# 2126_A_MatrixBoard_AffichageMatricielNom.net
KiCad netlist of a schematic drawn in Altium Designer
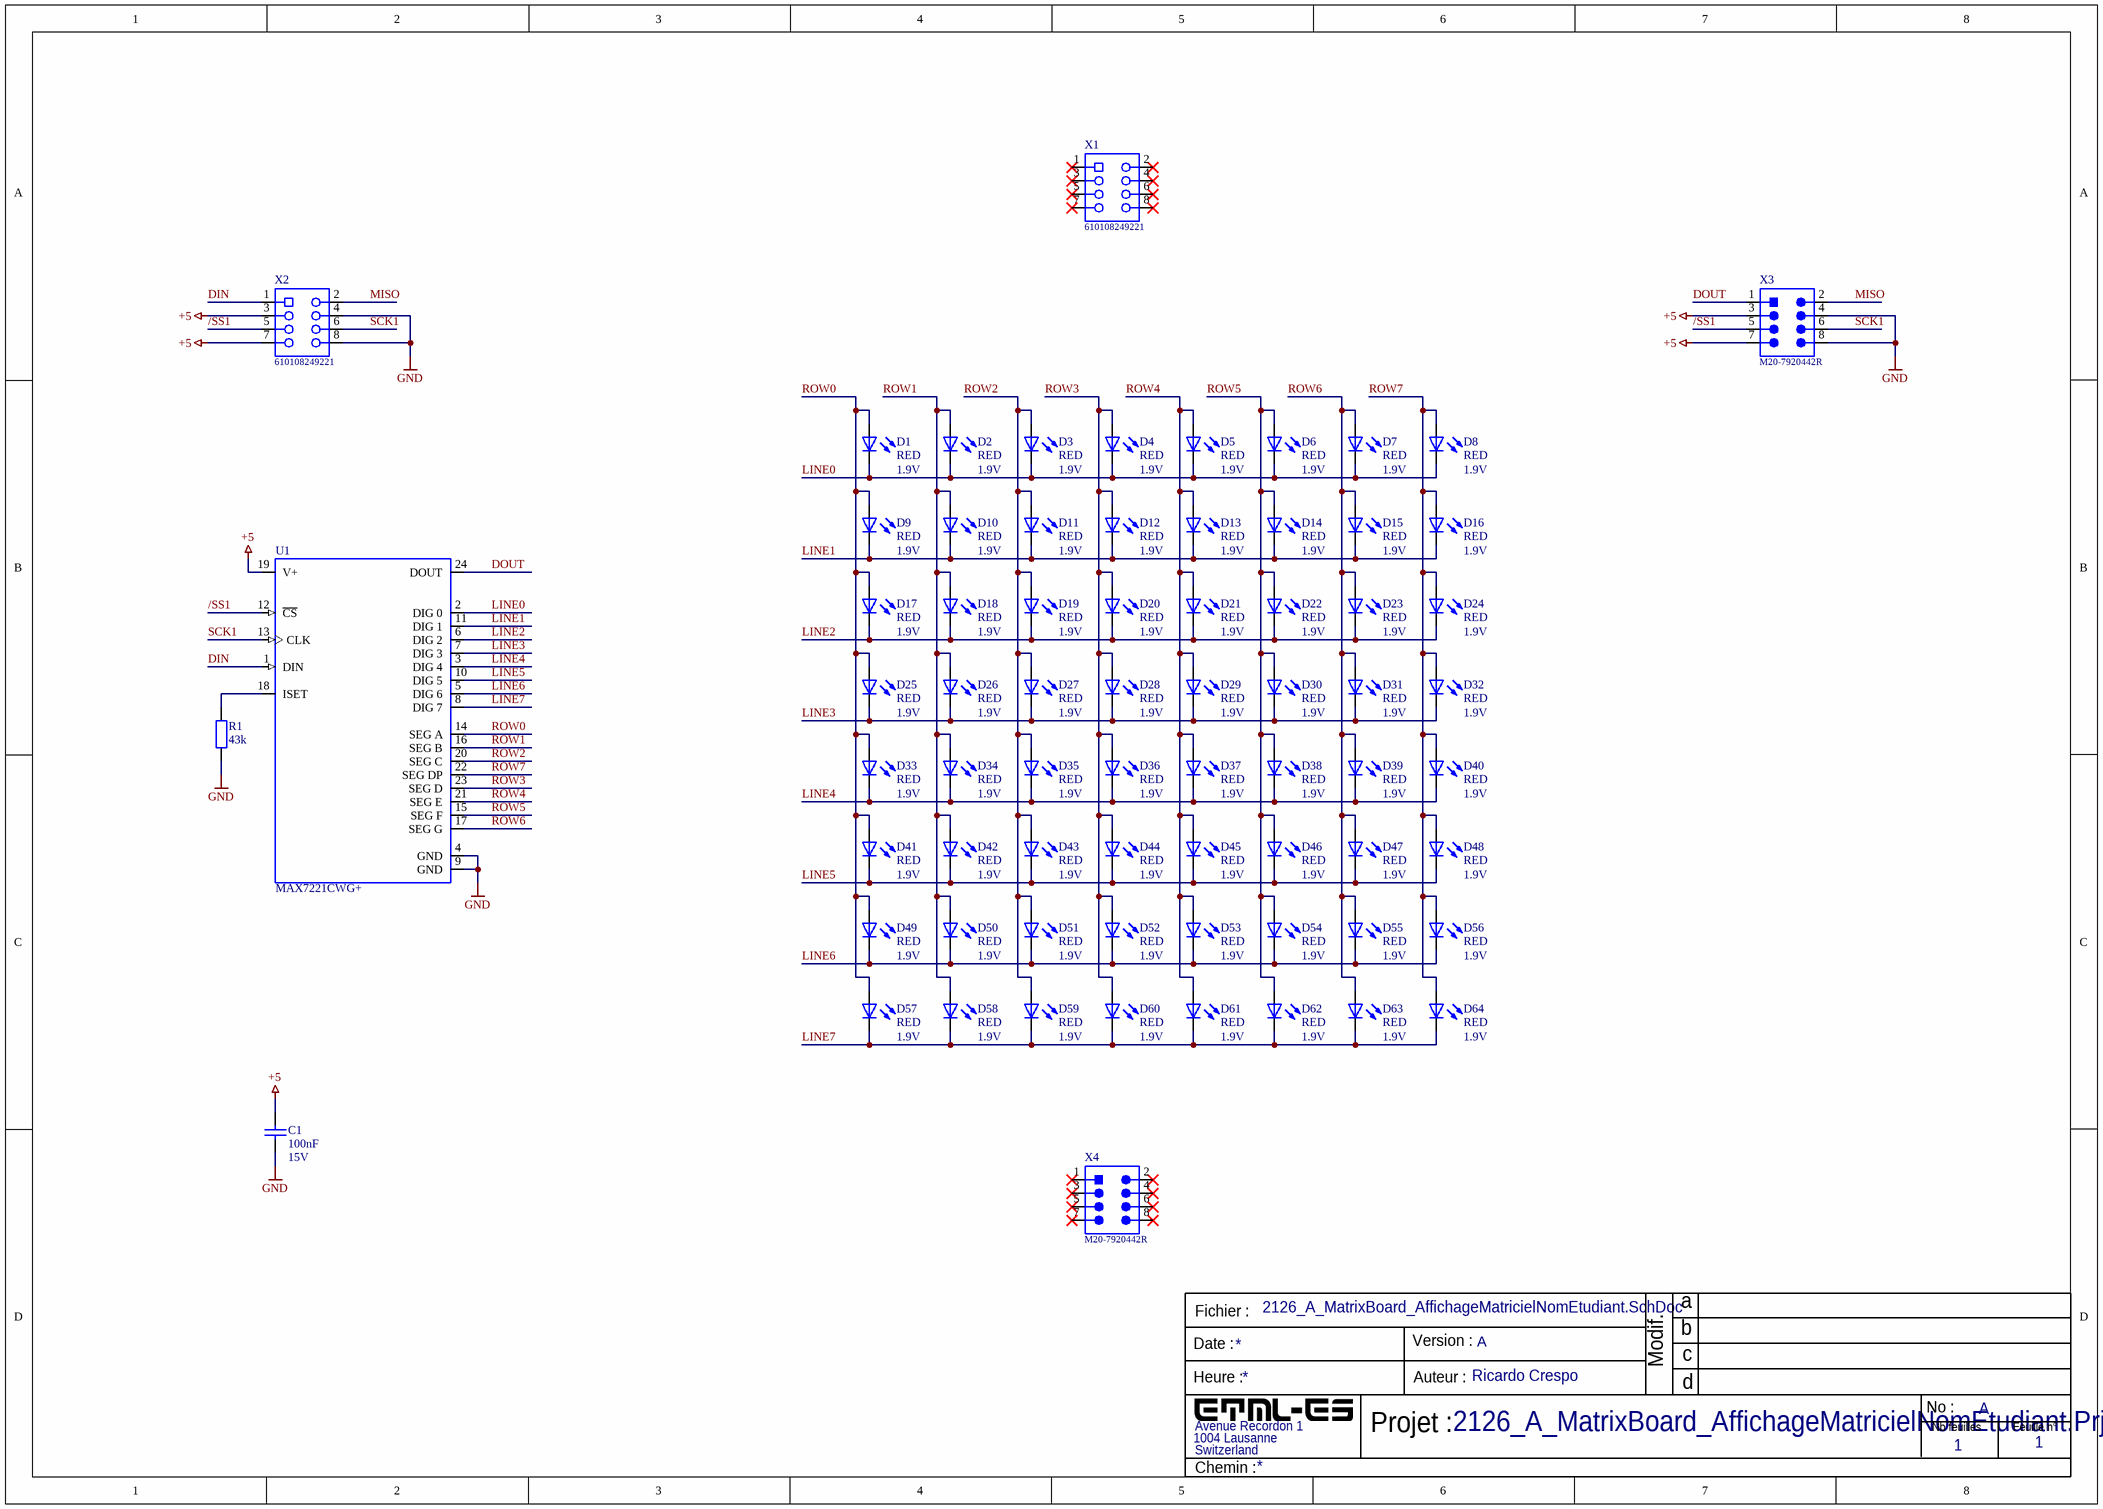
[diagram p0: 2126_A_MatrixBoard_AffichageMatricielNomEtudiant.SchDoc]

(export (version "E")
  (design (tool "Eeschema 10.0.6"))
  (components
    (comp (ref "C1")
      (value "100nF")
      (footprint "CAPC2013X145X48NL20T23")
      (description "VJ0805Y104KNAAT")
      (fields (field (name "MANUFACTURER") "Vitramon"))
      (libsource (lib "2126_AffichageMatriciel") (part "CMP-2007-03167-1"))
    )
    (comp (ref "D1")
      (value "RED")
      (footprint "SODFL350X210-2N")
      (description "WL-TMRC THT Mono-color Round Color, size 3mm, Bright Green, 2.1V, 40deg")
      (fields (field (name "PART NUMBER") "151031VS04000") (field (name "PUBLISHER") "Wurth Elektronik"))
      (libsource (lib "2126_AffichageMatriciel") (part "151031VS04000"))
    )
    (comp (ref "D2")
      (value "RED")
      (footprint "SODFL350X210-2N")
      (description "WL-TMRC THT Mono-color Round Color, size 3mm, Bright Green, 2.1V, 40deg")
      (fields (field (name "PART NUMBER") "151031VS04000") (field (name "PUBLISHER") "Wurth Elektronik"))
      (libsource (lib "2126_AffichageMatriciel") (part "151031VS04000"))
    )
    (comp (ref "D3")
      (value "RED")
      (footprint "SODFL350X210-2N")
      (description "WL-TMRC THT Mono-color Round Color, size 3mm, Bright Green, 2.1V, 40deg")
      (fields (field (name "PART NUMBER") "151031VS04000") (field (name "PUBLISHER") "Wurth Elektronik"))
      (libsource (lib "2126_AffichageMatriciel") (part "151031VS04000"))
    )
    (comp (ref "D4")
      (value "RED")
      (footprint "SODFL350X210-2N")
      (description "WL-TMRC THT Mono-color Round Color, size 3mm, Bright Green, 2.1V, 40deg")
      (fields (field (name "PART NUMBER") "151031VS04000") (field (name "PUBLISHER") "Wurth Elektronik"))
      (libsource (lib "2126_AffichageMatriciel") (part "151031VS04000"))
    )
    (comp (ref "D5")
      (value "RED")
      (footprint "SODFL350X210-2N")
      (description "WL-TMRC THT Mono-color Round Color, size 3mm, Bright Green, 2.1V, 40deg")
      (fields (field (name "PART NUMBER") "151031VS04000") (field (name "PUBLISHER") "Wurth Elektronik"))
      (libsource (lib "2126_AffichageMatriciel") (part "151031VS04000"))
    )
    (comp (ref "D6")
      (value "RED")
      (footprint "SODFL350X210-2N")
      (description "WL-TMRC THT Mono-color Round Color, size 3mm, Bright Green, 2.1V, 40deg")
      (fields (field (name "PART NUMBER") "151031VS04000") (field (name "PUBLISHER") "Wurth Elektronik"))
      (libsource (lib "2126_AffichageMatriciel") (part "151031VS04000"))
    )
    (comp (ref "D7")
      (value "RED")
      (footprint "SODFL350X210-2N")
      (description "WL-TMRC THT Mono-color Round Color, size 3mm, Bright Green, 2.1V, 40deg")
      (fields (field (name "PART NUMBER") "151031VS04000") (field (name "PUBLISHER") "Wurth Elektronik"))
      (libsource (lib "2126_AffichageMatriciel") (part "151031VS04000"))
    )
    (comp (ref "D8")
      (value "RED")
      (footprint "SODFL350X210-2N")
      (description "WL-TMRC THT Mono-color Round Color, size 3mm, Bright Green, 2.1V, 40deg")
      (fields (field (name "PART NUMBER") "151031VS04000") (field (name "PUBLISHER") "Wurth Elektronik"))
      (libsource (lib "2126_AffichageMatriciel") (part "151031VS04000"))
    )
    (comp (ref "D9")
      (value "RED")
      (footprint "SODFL350X210-2N")
      (description "WL-TMRC THT Mono-color Round Color, size 3mm, Bright Green, 2.1V, 40deg")
      (fields (field (name "PART NUMBER") "151031VS04000") (field (name "PUBLISHER") "Wurth Elektronik"))
      (libsource (lib "2126_AffichageMatriciel") (part "151031VS04000"))
    )
    (comp (ref "D10")
      (value "RED")
      (footprint "SODFL350X210-2N")
      (description "WL-TMRC THT Mono-color Round Color, size 3mm, Bright Green, 2.1V, 40deg")
      (fields (field (name "PART NUMBER") "151031VS04000") (field (name "PUBLISHER") "Wurth Elektronik"))
      (libsource (lib "2126_AffichageMatriciel") (part "151031VS04000"))
    )
    (comp (ref "D11")
      (value "RED")
      (footprint "SODFL350X210-2N")
      (description "WL-TMRC THT Mono-color Round Color, size 3mm, Bright Green, 2.1V, 40deg")
      (fields (field (name "PART NUMBER") "151031VS04000") (field (name "PUBLISHER") "Wurth Elektronik"))
      (libsource (lib "2126_AffichageMatriciel") (part "151031VS04000"))
    )
    (comp (ref "D12")
      (value "RED")
      (footprint "SODFL350X210-2N")
      (description "WL-TMRC THT Mono-color Round Color, size 3mm, Bright Green, 2.1V, 40deg")
      (fields (field (name "PART NUMBER") "151031VS04000") (field (name "PUBLISHER") "Wurth Elektronik"))
      (libsource (lib "2126_AffichageMatriciel") (part "151031VS04000"))
    )
    (comp (ref "D13")
      (value "RED")
      (footprint "SODFL350X210-2N")
      (description "WL-TMRC THT Mono-color Round Color, size 3mm, Bright Green, 2.1V, 40deg")
      (fields (field (name "PART NUMBER") "151031VS04000") (field (name "PUBLISHER") "Wurth Elektronik"))
      (libsource (lib "2126_AffichageMatriciel") (part "151031VS04000"))
    )
    (comp (ref "D14")
      (value "RED")
      (footprint "SODFL350X210-2N")
      (description "WL-TMRC THT Mono-color Round Color, size 3mm, Bright Green, 2.1V, 40deg")
      (fields (field (name "PART NUMBER") "151031VS04000") (field (name "PUBLISHER") "Wurth Elektronik"))
      (libsource (lib "2126_AffichageMatriciel") (part "151031VS04000"))
    )
    (comp (ref "D15")
      (value "RED")
      (footprint "SODFL350X210-2N")
      (description "WL-TMRC THT Mono-color Round Color, size 3mm, Bright Green, 2.1V, 40deg")
      (fields (field (name "PART NUMBER") "151031VS04000") (field (name "PUBLISHER") "Wurth Elektronik"))
      (libsource (lib "2126_AffichageMatriciel") (part "151031VS04000"))
    )
    (comp (ref "D16")
      (value "RED")
      (footprint "SODFL350X210-2N")
      (description "WL-TMRC THT Mono-color Round Color, size 3mm, Bright Green, 2.1V, 40deg")
      (fields (field (name "PART NUMBER") "151031VS04000") (field (name "PUBLISHER") "Wurth Elektronik"))
      (libsource (lib "2126_AffichageMatriciel") (part "151031VS04000"))
    )
    (comp (ref "D17")
      (value "RED")
      (footprint "SODFL350X210-2N")
      (description "WL-TMRC THT Mono-color Round Color, size 3mm, Bright Green, 2.1V, 40deg")
      (fields (field (name "PART NUMBER") "151031VS04000") (field (name "PUBLISHER") "Wurth Elektronik"))
      (libsource (lib "2126_AffichageMatriciel") (part "151031VS04000"))
    )
    (comp (ref "D18")
      (value "RED")
      (footprint "SODFL350X210-2N")
      (description "WL-TMRC THT Mono-color Round Color, size 3mm, Bright Green, 2.1V, 40deg")
      (fields (field (name "PART NUMBER") "151031VS04000") (field (name "PUBLISHER") "Wurth Elektronik"))
      (libsource (lib "2126_AffichageMatriciel") (part "151031VS04000"))
    )
    (comp (ref "D19")
      (value "RED")
      (footprint "SODFL350X210-2N")
      (description "WL-TMRC THT Mono-color Round Color, size 3mm, Bright Green, 2.1V, 40deg")
      (fields (field (name "PART NUMBER") "151031VS04000") (field (name "PUBLISHER") "Wurth Elektronik"))
      (libsource (lib "2126_AffichageMatriciel") (part "151031VS04000"))
    )
    (comp (ref "D20")
      (value "RED")
      (footprint "SODFL350X210-2N")
      (description "WL-TMRC THT Mono-color Round Color, size 3mm, Bright Green, 2.1V, 40deg")
      (fields (field (name "PART NUMBER") "151031VS04000") (field (name "PUBLISHER") "Wurth Elektronik"))
      (libsource (lib "2126_AffichageMatriciel") (part "151031VS04000"))
    )
    (comp (ref "D21")
      (value "RED")
      (footprint "SODFL350X210-2N")
      (description "WL-TMRC THT Mono-color Round Color, size 3mm, Bright Green, 2.1V, 40deg")
      (fields (field (name "PART NUMBER") "151031VS04000") (field (name "PUBLISHER") "Wurth Elektronik"))
      (libsource (lib "2126_AffichageMatriciel") (part "151031VS04000"))
    )
    (comp (ref "D22")
      (value "RED")
      (footprint "SODFL350X210-2N")
      (description "WL-TMRC THT Mono-color Round Color, size 3mm, Bright Green, 2.1V, 40deg")
      (fields (field (name "PART NUMBER") "151031VS04000") (field (name "PUBLISHER") "Wurth Elektronik"))
      (libsource (lib "2126_AffichageMatriciel") (part "151031VS04000"))
    )
    (comp (ref "D23")
      (value "RED")
      (footprint "SODFL350X210-2N")
      (description "WL-TMRC THT Mono-color Round Color, size 3mm, Bright Green, 2.1V, 40deg")
      (fields (field (name "PART NUMBER") "151031VS04000") (field (name "PUBLISHER") "Wurth Elektronik"))
      (libsource (lib "2126_AffichageMatriciel") (part "151031VS04000"))
    )
    (comp (ref "D24")
      (value "RED")
      (footprint "SODFL350X210-2N")
      (description "WL-TMRC THT Mono-color Round Color, size 3mm, Bright Green, 2.1V, 40deg")
      (fields (field (name "PART NUMBER") "151031VS04000") (field (name "PUBLISHER") "Wurth Elektronik"))
      (libsource (lib "2126_AffichageMatriciel") (part "151031VS04000"))
    )
    (comp (ref "D25")
      (value "RED")
      (footprint "SODFL350X210-2N")
      (description "WL-TMRC THT Mono-color Round Color, size 3mm, Bright Green, 2.1V, 40deg")
      (fields (field (name "PART NUMBER") "151031VS04000") (field (name "PUBLISHER") "Wurth Elektronik"))
      (libsource (lib "2126_AffichageMatriciel") (part "151031VS04000"))
    )
    (comp (ref "D26")
      (value "RED")
      (footprint "SODFL350X210-2N")
      (description "WL-TMRC THT Mono-color Round Color, size 3mm, Bright Green, 2.1V, 40deg")
      (fields (field (name "PART NUMBER") "151031VS04000") (field (name "PUBLISHER") "Wurth Elektronik"))
      (libsource (lib "2126_AffichageMatriciel") (part "151031VS04000"))
    )
    (comp (ref "D27")
      (value "RED")
      (footprint "SODFL350X210-2N")
      (description "WL-TMRC THT Mono-color Round Color, size 3mm, Bright Green, 2.1V, 40deg")
      (fields (field (name "PART NUMBER") "151031VS04000") (field (name "PUBLISHER") "Wurth Elektronik"))
      (libsource (lib "2126_AffichageMatriciel") (part "151031VS04000"))
    )
    (comp (ref "D28")
      (value "RED")
      (footprint "SODFL350X210-2N")
      (description "WL-TMRC THT Mono-color Round Color, size 3mm, Bright Green, 2.1V, 40deg")
      (fields (field (name "PART NUMBER") "151031VS04000") (field (name "PUBLISHER") "Wurth Elektronik"))
      (libsource (lib "2126_AffichageMatriciel") (part "151031VS04000"))
    )
    (comp (ref "D29")
      (value "RED")
      (footprint "SODFL350X210-2N")
      (description "WL-TMRC THT Mono-color Round Color, size 3mm, Bright Green, 2.1V, 40deg")
      (fields (field (name "PART NUMBER") "151031VS04000") (field (name "PUBLISHER") "Wurth Elektronik"))
      (libsource (lib "2126_AffichageMatriciel") (part "151031VS04000"))
    )
    (comp (ref "D30")
      (value "RED")
      (footprint "SODFL350X210-2N")
      (description "WL-TMRC THT Mono-color Round Color, size 3mm, Bright Green, 2.1V, 40deg")
      (fields (field (name "PART NUMBER") "151031VS04000") (field (name "PUBLISHER") "Wurth Elektronik"))
      (libsource (lib "2126_AffichageMatriciel") (part "151031VS04000"))
    )
    (comp (ref "D31")
      (value "RED")
      (footprint "SODFL350X210-2N")
      (description "WL-TMRC THT Mono-color Round Color, size 3mm, Bright Green, 2.1V, 40deg")
      (fields (field (name "PART NUMBER") "151031VS04000") (field (name "PUBLISHER") "Wurth Elektronik"))
      (libsource (lib "2126_AffichageMatriciel") (part "151031VS04000"))
    )
    (comp (ref "D32")
      (value "RED")
      (footprint "SODFL350X210-2N")
      (description "WL-TMRC THT Mono-color Round Color, size 3mm, Bright Green, 2.1V, 40deg")
      (fields (field (name "PART NUMBER") "151031VS04000") (field (name "PUBLISHER") "Wurth Elektronik"))
      (libsource (lib "2126_AffichageMatriciel") (part "151031VS04000"))
    )
    (comp (ref "D33")
      (value "RED")
      (footprint "SODFL350X210-2N")
      (description "WL-TMRC THT Mono-color Round Color, size 3mm, Bright Green, 2.1V, 40deg")
      (fields (field (name "PART NUMBER") "151031VS04000") (field (name "PUBLISHER") "Wurth Elektronik"))
      (libsource (lib "2126_AffichageMatriciel") (part "151031VS04000"))
    )
    (comp (ref "D34")
      (value "RED")
      (footprint "SODFL350X210-2N")
      (description "WL-TMRC THT Mono-color Round Color, size 3mm, Bright Green, 2.1V, 40deg")
      (fields (field (name "PART NUMBER") "151031VS04000") (field (name "PUBLISHER") "Wurth Elektronik"))
      (libsource (lib "2126_AffichageMatriciel") (part "151031VS04000"))
    )
    (comp (ref "D35")
      (value "RED")
      (footprint "SODFL350X210-2N")
      (description "WL-TMRC THT Mono-color Round Color, size 3mm, Bright Green, 2.1V, 40deg")
      (fields (field (name "PART NUMBER") "151031VS04000") (field (name "PUBLISHER") "Wurth Elektronik"))
      (libsource (lib "2126_AffichageMatriciel") (part "151031VS04000"))
    )
    (comp (ref "D36")
      (value "RED")
      (footprint "SODFL350X210-2N")
      (description "WL-TMRC THT Mono-color Round Color, size 3mm, Bright Green, 2.1V, 40deg")
      (fields (field (name "PART NUMBER") "151031VS04000") (field (name "PUBLISHER") "Wurth Elektronik"))
      (libsource (lib "2126_AffichageMatriciel") (part "151031VS04000"))
    )
    (comp (ref "D37")
      (value "RED")
      (footprint "SODFL350X210-2N")
      (description "WL-TMRC THT Mono-color Round Color, size 3mm, Bright Green, 2.1V, 40deg")
      (fields (field (name "PART NUMBER") "151031VS04000") (field (name "PUBLISHER") "Wurth Elektronik"))
      (libsource (lib "2126_AffichageMatriciel") (part "151031VS04000"))
    )
    (comp (ref "D38")
      (value "RED")
      (footprint "SODFL350X210-2N")
      (description "WL-TMRC THT Mono-color Round Color, size 3mm, Bright Green, 2.1V, 40deg")
      (fields (field (name "PART NUMBER") "151031VS04000") (field (name "PUBLISHER") "Wurth Elektronik"))
      (libsource (lib "2126_AffichageMatriciel") (part "151031VS04000"))
    )
    (comp (ref "D39")
      (value "RED")
      (footprint "SODFL350X210-2N")
      (description "WL-TMRC THT Mono-color Round Color, size 3mm, Bright Green, 2.1V, 40deg")
      (fields (field (name "PART NUMBER") "151031VS04000") (field (name "PUBLISHER") "Wurth Elektronik"))
      (libsource (lib "2126_AffichageMatriciel") (part "151031VS04000"))
    )
    (comp (ref "D40")
      (value "RED")
      (footprint "SODFL350X210-2N")
      (description "WL-TMRC THT Mono-color Round Color, size 3mm, Bright Green, 2.1V, 40deg")
      (fields (field (name "PART NUMBER") "151031VS04000") (field (name "PUBLISHER") "Wurth Elektronik"))
      (libsource (lib "2126_AffichageMatriciel") (part "151031VS04000"))
    )
    (comp (ref "D41")
      (value "RED")
      (footprint "SODFL350X210-2N")
      (description "WL-TMRC THT Mono-color Round Color, size 3mm, Bright Green, 2.1V, 40deg")
      (fields (field (name "PART NUMBER") "151031VS04000") (field (name "PUBLISHER") "Wurth Elektronik"))
      (libsource (lib "2126_AffichageMatriciel") (part "151031VS04000"))
    )
    (comp (ref "D42")
      (value "RED")
      (footprint "SODFL350X210-2N")
      (description "WL-TMRC THT Mono-color Round Color, size 3mm, Bright Green, 2.1V, 40deg")
      (fields (field (name "PART NUMBER") "151031VS04000") (field (name "PUBLISHER") "Wurth Elektronik"))
      (libsource (lib "2126_AffichageMatriciel") (part "151031VS04000"))
    )
    (comp (ref "D43")
      (value "RED")
      (footprint "SODFL350X210-2N")
      (description "WL-TMRC THT Mono-color Round Color, size 3mm, Bright Green, 2.1V, 40deg")
      (fields (field (name "PART NUMBER") "151031VS04000") (field (name "PUBLISHER") "Wurth Elektronik"))
      (libsource (lib "2126_AffichageMatriciel") (part "151031VS04000"))
    )
    (comp (ref "D44")
      (value "RED")
      (footprint "SODFL350X210-2N")
      (description "WL-TMRC THT Mono-color Round Color, size 3mm, Bright Green, 2.1V, 40deg")
      (fields (field (name "PART NUMBER") "151031VS04000") (field (name "PUBLISHER") "Wurth Elektronik"))
      (libsource (lib "2126_AffichageMatriciel") (part "151031VS04000"))
    )
    (comp (ref "D45")
      (value "RED")
      (footprint "SODFL350X210-2N")
      (description "WL-TMRC THT Mono-color Round Color, size 3mm, Bright Green, 2.1V, 40deg")
      (fields (field (name "PART NUMBER") "151031VS04000") (field (name "PUBLISHER") "Wurth Elektronik"))
      (libsource (lib "2126_AffichageMatriciel") (part "151031VS04000"))
    )
    (comp (ref "D46")
      (value "RED")
      (footprint "SODFL350X210-2N")
      (description "WL-TMRC THT Mono-color Round Color, size 3mm, Bright Green, 2.1V, 40deg")
      (fields (field (name "PART NUMBER") "151031VS04000") (field (name "PUBLISHER") "Wurth Elektronik"))
      (libsource (lib "2126_AffichageMatriciel") (part "151031VS04000"))
    )
    (comp (ref "D47")
      (value "RED")
      (footprint "SODFL350X210-2N")
      (description "WL-TMRC THT Mono-color Round Color, size 3mm, Bright Green, 2.1V, 40deg")
      (fields (field (name "PART NUMBER") "151031VS04000") (field (name "PUBLISHER") "Wurth Elektronik"))
      (libsource (lib "2126_AffichageMatriciel") (part "151031VS04000"))
    )
    (comp (ref "D48")
      (value "RED")
      (footprint "SODFL350X210-2N")
      (description "WL-TMRC THT Mono-color Round Color, size 3mm, Bright Green, 2.1V, 40deg")
      (fields (field (name "PART NUMBER") "151031VS04000") (field (name "PUBLISHER") "Wurth Elektronik"))
      (libsource (lib "2126_AffichageMatriciel") (part "151031VS04000"))
    )
    (comp (ref "D49")
      (value "RED")
      (footprint "SODFL350X210-2N")
      (description "WL-TMRC THT Mono-color Round Color, size 3mm, Bright Green, 2.1V, 40deg")
      (fields (field (name "PART NUMBER") "151031VS04000") (field (name "PUBLISHER") "Wurth Elektronik"))
      (libsource (lib "2126_AffichageMatriciel") (part "151031VS04000"))
    )
    (comp (ref "D50")
      (value "RED")
      (footprint "SODFL350X210-2N")
      (description "WL-TMRC THT Mono-color Round Color, size 3mm, Bright Green, 2.1V, 40deg")
      (fields (field (name "PART NUMBER") "151031VS04000") (field (name "PUBLISHER") "Wurth Elektronik"))
      (libsource (lib "2126_AffichageMatriciel") (part "151031VS04000"))
    )
    (comp (ref "D51")
      (value "RED")
      (footprint "SODFL350X210-2N")
      (description "WL-TMRC THT Mono-color Round Color, size 3mm, Bright Green, 2.1V, 40deg")
      (fields (field (name "PART NUMBER") "151031VS04000") (field (name "PUBLISHER") "Wurth Elektronik"))
      (libsource (lib "2126_AffichageMatriciel") (part "151031VS04000"))
    )
    (comp (ref "D52")
      (value "RED")
      (footprint "SODFL350X210-2N")
      (description "WL-TMRC THT Mono-color Round Color, size 3mm, Bright Green, 2.1V, 40deg")
      (fields (field (name "PART NUMBER") "151031VS04000") (field (name "PUBLISHER") "Wurth Elektronik"))
      (libsource (lib "2126_AffichageMatriciel") (part "151031VS04000"))
    )
    (comp (ref "D53")
      (value "RED")
      (footprint "SODFL350X210-2N")
      (description "WL-TMRC THT Mono-color Round Color, size 3mm, Bright Green, 2.1V, 40deg")
      (fields (field (name "PART NUMBER") "151031VS04000") (field (name "PUBLISHER") "Wurth Elektronik"))
      (libsource (lib "2126_AffichageMatriciel") (part "151031VS04000"))
    )
    (comp (ref "D54")
      (value "RED")
      (footprint "SODFL350X210-2N")
      (description "WL-TMRC THT Mono-color Round Color, size 3mm, Bright Green, 2.1V, 40deg")
      (fields (field (name "PART NUMBER") "151031VS04000") (field (name "PUBLISHER") "Wurth Elektronik"))
      (libsource (lib "2126_AffichageMatriciel") (part "151031VS04000"))
    )
    (comp (ref "D55")
      (value "RED")
      (footprint "SODFL350X210-2N")
      (description "WL-TMRC THT Mono-color Round Color, size 3mm, Bright Green, 2.1V, 40deg")
      (fields (field (name "PART NUMBER") "151031VS04000") (field (name "PUBLISHER") "Wurth Elektronik"))
      (libsource (lib "2126_AffichageMatriciel") (part "151031VS04000"))
    )
    (comp (ref "D56")
      (value "RED")
      (footprint "SODFL350X210-2N")
      (description "WL-TMRC THT Mono-color Round Color, size 3mm, Bright Green, 2.1V, 40deg")
      (fields (field (name "PART NUMBER") "151031VS04000") (field (name "PUBLISHER") "Wurth Elektronik"))
      (libsource (lib "2126_AffichageMatriciel") (part "151031VS04000"))
    )
    (comp (ref "D57")
      (value "RED")
      (footprint "SODFL350X210-2N")
      (description "WL-TMRC THT Mono-color Round Color, size 3mm, Bright Green, 2.1V, 40deg")
      (fields (field (name "PART NUMBER") "151031VS04000") (field (name "PUBLISHER") "Wurth Elektronik"))
      (libsource (lib "2126_AffichageMatriciel") (part "151031VS04000"))
    )
    (comp (ref "D58")
      (value "RED")
      (footprint "SODFL350X210-2N")
      (description "WL-TMRC THT Mono-color Round Color, size 3mm, Bright Green, 2.1V, 40deg")
      (fields (field (name "PART NUMBER") "151031VS04000") (field (name "PUBLISHER") "Wurth Elektronik"))
      (libsource (lib "2126_AffichageMatriciel") (part "151031VS04000"))
    )
    (comp (ref "D59")
      (value "RED")
      (footprint "SODFL350X210-2N")
      (description "WL-TMRC THT Mono-color Round Color, size 3mm, Bright Green, 2.1V, 40deg")
      (fields (field (name "PART NUMBER") "151031VS04000") (field (name "PUBLISHER") "Wurth Elektronik"))
      (libsource (lib "2126_AffichageMatriciel") (part "151031VS04000"))
    )
    (comp (ref "D60")
      (value "RED")
      (footprint "SODFL350X210-2N")
      (description "WL-TMRC THT Mono-color Round Color, size 3mm, Bright Green, 2.1V, 40deg")
      (fields (field (name "PART NUMBER") "151031VS04000") (field (name "PUBLISHER") "Wurth Elektronik"))
      (libsource (lib "2126_AffichageMatriciel") (part "151031VS04000"))
    )
    (comp (ref "D61")
      (value "RED")
      (footprint "SODFL350X210-2N")
      (description "WL-TMRC THT Mono-color Round Color, size 3mm, Bright Green, 2.1V, 40deg")
      (fields (field (name "PART NUMBER") "151031VS04000") (field (name "PUBLISHER") "Wurth Elektronik"))
      (libsource (lib "2126_AffichageMatriciel") (part "151031VS04000"))
    )
    (comp (ref "D62")
      (value "RED")
      (footprint "SODFL350X210-2N")
      (description "WL-TMRC THT Mono-color Round Color, size 3mm, Bright Green, 2.1V, 40deg")
      (fields (field (name "PART NUMBER") "151031VS04000") (field (name "PUBLISHER") "Wurth Elektronik"))
      (libsource (lib "2126_AffichageMatriciel") (part "151031VS04000"))
    )
    (comp (ref "D63")
      (value "RED")
      (footprint "SODFL350X210-2N")
      (description "WL-TMRC THT Mono-color Round Color, size 3mm, Bright Green, 2.1V, 40deg")
      (fields (field (name "PART NUMBER") "151031VS04000") (field (name "PUBLISHER") "Wurth Elektronik"))
      (libsource (lib "2126_AffichageMatriciel") (part "151031VS04000"))
    )
    (comp (ref "D64")
      (value "RED")
      (footprint "SODFL350X210-2N")
      (description "WL-TMRC THT Mono-color Round Color, size 3mm, Bright Green, 2.1V, 40deg")
      (fields (field (name "PART NUMBER") "151031VS04000") (field (name "PUBLISHER") "Wurth Elektronik"))
      (libsource (lib "2126_AffichageMatriciel") (part "151031VS04000"))
    )
    (comp (ref "R1")
      (value "43k")
      (footprint "RESC2013X70X40ML20T20")
      (description "10K 0.125W 1% 0805 (2012 Metric)  SMD")
      (fields (field (name "TOLERANCE") "1 %") (field (name "POWER") "0.125 W"))
      (libsource (lib "2126_AffichageMatriciel") (part "CMP-1013-00623-1"))
    )
    (comp (ref "U1")
      (value "MAX7221CWG+")
      (footprint "FP-W24-1-IPC_B")
      (description "IC DRVR 7 SEGMNT 8 DIGIT 24SOIC")
      (fields
        (field (name "MANUFACTURER") "Maxim Integrated")
        (field (name "OCTOPART") "https://octopart.com/max7221cwg%2B-maxim+integrated-39581478")
      )
      (libsource (lib "2126_AffichageMatriciel") (part "CMP-05718-000002-1"))
    )
    (comp (ref "X1")
      (value "610108249221")
      (footprint "610108249221")
      (description "WR-PHD Socket Header, THT, pitch 2.54mm, Dual Row, Angled, 8p")
      (fields
        (field (name "MANUFACTURER PART NUMBER") "613008243121")
        (field (name "MANUFACTURER") "Wurth Elektronik")
      )
      (libsource (lib "2126_AffichageMatriciel") (part "610108249221"))
    )
    (comp (ref "X2")
      (value "610108249221")
      (footprint "610108249221")
      (description "WR-PHD Socket Header, THT, pitch 2.54mm, Dual Row, Angled, 8p")
      (fields
        (field (name "MANUFACTURER PART NUMBER") "613008243121")
        (field (name "MANUFACTURER") "Wurth Elektronik")
      )
      (libsource (lib "2126_AffichageMatriciel") (part "610108249221"))
    )
    (comp (ref "X3")
      (value "M20-7920442R")
      (footprint "610108249121")
      (description "WR-PHD Pin Header, THT, pitch 2.54mm, Dual Row, Angled, 8p")
      (fields
        (field (name "MANUFACTURER PART NUMBER") "61300821021")
        (field (name "MANUFACTURER") "Wurth Elektronik")
      )
      (libsource (lib "2126_AffichageMatriciel") (part "610108249121"))
    )
    (comp (ref "X4")
      (value "M20-7920442R")
      (footprint "610108249121")
      (description "WR-PHD Pin Header, THT, pitch 2.54mm, Dual Row, Angled, 8p")
      (fields
        (field (name "MANUFACTURER PART NUMBER") "61300821021")
        (field (name "MANUFACTURER") "Wurth Elektronik")
      )
      (libsource (lib "2126_AffichageMatriciel") (part "610108249121"))
    )
  )
  (nets
    (net (code "1") (name "+5") (class "Default")
      (node (ref "C1") (pin "2") (pinfunction "2_2") (pintype "passive"))
      (node (ref "U1") (pin "19") (pinfunction "V+_19") (pintype "power_in"))
      (node (ref "X2") (pin "3") (pinfunction "3_3") (pintype "passive"))
      (node (ref "X2") (pin "7") (pinfunction "7_7") (pintype "passive"))
      (node (ref "X3") (pin "3") (pinfunction "3_3") (pintype "passive"))
      (node (ref "X3") (pin "7") (pinfunction "7_7") (pintype "passive"))
    )
    (net (code "2") (name "/DIN") (class "Default")
      (node (ref "U1") (pin "1") (pinfunction "DIN_1") (pintype "input"))
      (node (ref "X2") (pin "1") (pinfunction "1_1") (pintype "passive"))
    )
    (net (code "3") (name "/DOUT") (class "Default")
      (node (ref "U1") (pin "24") (pinfunction "DOUT_24") (pintype "passive"))
      (node (ref "X3") (pin "1") (pinfunction "1_1") (pintype "passive"))
    )
    (net (code "4") (name "/LINE0") (class "Default")
      (node (ref "D1") (pin "K") (pinfunction "K_K") (pintype "passive"))
      (node (ref "D2") (pin "K") (pinfunction "K_K") (pintype "passive"))
      (node (ref "D3") (pin "K") (pinfunction "K_K") (pintype "passive"))
      (node (ref "D4") (pin "K") (pinfunction "K_K") (pintype "passive"))
      (node (ref "D5") (pin "K") (pinfunction "K_K") (pintype "passive"))
      (node (ref "D6") (pin "K") (pinfunction "K_K") (pintype "passive"))
      (node (ref "D7") (pin "K") (pinfunction "K_K") (pintype "passive"))
      (node (ref "D8") (pin "K") (pinfunction "K_K") (pintype "passive"))
      (node (ref "U1") (pin "2") (pinfunction "DIG_0_2") (pintype "passive"))
    )
    (net (code "5") (name "/LINE1") (class "Default")
      (node (ref "D10") (pin "K") (pinfunction "K_K") (pintype "passive"))
      (node (ref "D11") (pin "K") (pinfunction "K_K") (pintype "passive"))
      (node (ref "D12") (pin "K") (pinfunction "K_K") (pintype "passive"))
      (node (ref "D13") (pin "K") (pinfunction "K_K") (pintype "passive"))
      (node (ref "D14") (pin "K") (pinfunction "K_K") (pintype "passive"))
      (node (ref "D15") (pin "K") (pinfunction "K_K") (pintype "passive"))
      (node (ref "D16") (pin "K") (pinfunction "K_K") (pintype "passive"))
      (node (ref "D9") (pin "K") (pinfunction "K_K") (pintype "passive"))
      (node (ref "U1") (pin "11") (pinfunction "DIG_1_11") (pintype "passive"))
    )
    (net (code "6") (name "/LINE2") (class "Default")
      (node (ref "D17") (pin "K") (pinfunction "K_K") (pintype "passive"))
      (node (ref "D18") (pin "K") (pinfunction "K_K") (pintype "passive"))
      (node (ref "D19") (pin "K") (pinfunction "K_K") (pintype "passive"))
      (node (ref "D20") (pin "K") (pinfunction "K_K") (pintype "passive"))
      (node (ref "D21") (pin "K") (pinfunction "K_K") (pintype "passive"))
      (node (ref "D22") (pin "K") (pinfunction "K_K") (pintype "passive"))
      (node (ref "D23") (pin "K") (pinfunction "K_K") (pintype "passive"))
      (node (ref "D24") (pin "K") (pinfunction "K_K") (pintype "passive"))
      (node (ref "U1") (pin "6") (pinfunction "DIG_2_6") (pintype "passive"))
    )
    (net (code "7") (name "/LINE3") (class "Default")
      (node (ref "D25") (pin "K") (pinfunction "K_K") (pintype "passive"))
      (node (ref "D26") (pin "K") (pinfunction "K_K") (pintype "passive"))
      (node (ref "D27") (pin "K") (pinfunction "K_K") (pintype "passive"))
      (node (ref "D28") (pin "K") (pinfunction "K_K") (pintype "passive"))
      (node (ref "D29") (pin "K") (pinfunction "K_K") (pintype "passive"))
      (node (ref "D30") (pin "K") (pinfunction "K_K") (pintype "passive"))
      (node (ref "D31") (pin "K") (pinfunction "K_K") (pintype "passive"))
      (node (ref "D32") (pin "K") (pinfunction "K_K") (pintype "passive"))
      (node (ref "U1") (pin "7") (pinfunction "DIG_3_7") (pintype "passive"))
    )
    (net (code "8") (name "/LINE4") (class "Default")
      (node (ref "D33") (pin "K") (pinfunction "K_K") (pintype "passive"))
      (node (ref "D34") (pin "K") (pinfunction "K_K") (pintype "passive"))
      (node (ref "D35") (pin "K") (pinfunction "K_K") (pintype "passive"))
      (node (ref "D36") (pin "K") (pinfunction "K_K") (pintype "passive"))
      (node (ref "D37") (pin "K") (pinfunction "K_K") (pintype "passive"))
      (node (ref "D38") (pin "K") (pinfunction "K_K") (pintype "passive"))
      (node (ref "D39") (pin "K") (pinfunction "K_K") (pintype "passive"))
      (node (ref "D40") (pin "K") (pinfunction "K_K") (pintype "passive"))
      (node (ref "U1") (pin "3") (pinfunction "DIG_4_3") (pintype "passive"))
    )
    (net (code "9") (name "/LINE5") (class "Default")
      (node (ref "D41") (pin "K") (pinfunction "K_K") (pintype "passive"))
      (node (ref "D42") (pin "K") (pinfunction "K_K") (pintype "passive"))
      (node (ref "D43") (pin "K") (pinfunction "K_K") (pintype "passive"))
      (node (ref "D44") (pin "K") (pinfunction "K_K") (pintype "passive"))
      (node (ref "D45") (pin "K") (pinfunction "K_K") (pintype "passive"))
      (node (ref "D46") (pin "K") (pinfunction "K_K") (pintype "passive"))
      (node (ref "D47") (pin "K") (pinfunction "K_K") (pintype "passive"))
      (node (ref "D48") (pin "K") (pinfunction "K_K") (pintype "passive"))
      (node (ref "U1") (pin "10") (pinfunction "DIG_5_10") (pintype "passive"))
    )
    (net (code "10") (name "/LINE6") (class "Default")
      (node (ref "D49") (pin "K") (pinfunction "K_K") (pintype "passive"))
      (node (ref "D50") (pin "K") (pinfunction "K_K") (pintype "passive"))
      (node (ref "D51") (pin "K") (pinfunction "K_K") (pintype "passive"))
      (node (ref "D52") (pin "K") (pinfunction "K_K") (pintype "passive"))
      (node (ref "D53") (pin "K") (pinfunction "K_K") (pintype "passive"))
      (node (ref "D54") (pin "K") (pinfunction "K_K") (pintype "passive"))
      (node (ref "D55") (pin "K") (pinfunction "K_K") (pintype "passive"))
      (node (ref "D56") (pin "K") (pinfunction "K_K") (pintype "passive"))
      (node (ref "U1") (pin "5") (pinfunction "DIG_6_5") (pintype "passive"))
    )
    (net (code "11") (name "/LINE7") (class "Default")
      (node (ref "D57") (pin "K") (pinfunction "K_K") (pintype "passive"))
      (node (ref "D58") (pin "K") (pinfunction "K_K") (pintype "passive"))
      (node (ref "D59") (pin "K") (pinfunction "K_K") (pintype "passive"))
      (node (ref "D60") (pin "K") (pinfunction "K_K") (pintype "passive"))
      (node (ref "D61") (pin "K") (pinfunction "K_K") (pintype "passive"))
      (node (ref "D62") (pin "K") (pinfunction "K_K") (pintype "passive"))
      (node (ref "D63") (pin "K") (pinfunction "K_K") (pintype "passive"))
      (node (ref "D64") (pin "K") (pinfunction "K_K") (pintype "passive"))
      (node (ref "U1") (pin "8") (pinfunction "DIG_7_8") (pintype "passive"))
    )
    (net (code "12") (name "/MISO") (class "Default")
      (node (ref "X2") (pin "2") (pinfunction "2_2") (pintype "passive"))
      (node (ref "X3") (pin "2") (pinfunction "2_2") (pintype "passive"))
    )
    (net (code "13") (name "/ROW0") (class "Default")
      (node (ref "D1") (pin "A") (pinfunction "A_A") (pintype "passive"))
      (node (ref "D17") (pin "A") (pinfunction "A_A") (pintype "passive"))
      (node (ref "D25") (pin "A") (pinfunction "A_A") (pintype "passive"))
      (node (ref "D33") (pin "A") (pinfunction "A_A") (pintype "passive"))
      (node (ref "D41") (pin "A") (pinfunction "A_A") (pintype "passive"))
      (node (ref "D49") (pin "A") (pinfunction "A_A") (pintype "passive"))
      (node (ref "D57") (pin "A") (pinfunction "A_A") (pintype "passive"))
      (node (ref "D9") (pin "A") (pinfunction "A_A") (pintype "passive"))
      (node (ref "U1") (pin "14") (pinfunction "SEG_A_14") (pintype "passive"))
    )
    (net (code "14") (name "/ROW1") (class "Default")
      (node (ref "D10") (pin "A") (pinfunction "A_A") (pintype "passive"))
      (node (ref "D18") (pin "A") (pinfunction "A_A") (pintype "passive"))
      (node (ref "D2") (pin "A") (pinfunction "A_A") (pintype "passive"))
      (node (ref "D26") (pin "A") (pinfunction "A_A") (pintype "passive"))
      (node (ref "D34") (pin "A") (pinfunction "A_A") (pintype "passive"))
      (node (ref "D42") (pin "A") (pinfunction "A_A") (pintype "passive"))
      (node (ref "D50") (pin "A") (pinfunction "A_A") (pintype "passive"))
      (node (ref "D58") (pin "A") (pinfunction "A_A") (pintype "passive"))
      (node (ref "U1") (pin "16") (pinfunction "SEG_B_16") (pintype "passive"))
    )
    (net (code "15") (name "/ROW2") (class "Default")
      (node (ref "D11") (pin "A") (pinfunction "A_A") (pintype "passive"))
      (node (ref "D19") (pin "A") (pinfunction "A_A") (pintype "passive"))
      (node (ref "D27") (pin "A") (pinfunction "A_A") (pintype "passive"))
      (node (ref "D3") (pin "A") (pinfunction "A_A") (pintype "passive"))
      (node (ref "D35") (pin "A") (pinfunction "A_A") (pintype "passive"))
      (node (ref "D43") (pin "A") (pinfunction "A_A") (pintype "passive"))
      (node (ref "D51") (pin "A") (pinfunction "A_A") (pintype "passive"))
      (node (ref "D59") (pin "A") (pinfunction "A_A") (pintype "passive"))
      (node (ref "U1") (pin "20") (pinfunction "SEG_C_20") (pintype "passive"))
    )
    (net (code "16") (name "/ROW3") (class "Default")
      (node (ref "D12") (pin "A") (pinfunction "A_A") (pintype "passive"))
      (node (ref "D20") (pin "A") (pinfunction "A_A") (pintype "passive"))
      (node (ref "D28") (pin "A") (pinfunction "A_A") (pintype "passive"))
      (node (ref "D36") (pin "A") (pinfunction "A_A") (pintype "passive"))
      (node (ref "D4") (pin "A") (pinfunction "A_A") (pintype "passive"))
      (node (ref "D44") (pin "A") (pinfunction "A_A") (pintype "passive"))
      (node (ref "D52") (pin "A") (pinfunction "A_A") (pintype "passive"))
      (node (ref "D60") (pin "A") (pinfunction "A_A") (pintype "passive"))
      (node (ref "U1") (pin "23") (pinfunction "SEG_D_23") (pintype "passive"))
    )
    (net (code "17") (name "/ROW4") (class "Default")
      (node (ref "D13") (pin "A") (pinfunction "A_A") (pintype "passive"))
      (node (ref "D21") (pin "A") (pinfunction "A_A") (pintype "passive"))
      (node (ref "D29") (pin "A") (pinfunction "A_A") (pintype "passive"))
      (node (ref "D37") (pin "A") (pinfunction "A_A") (pintype "passive"))
      (node (ref "D45") (pin "A") (pinfunction "A_A") (pintype "passive"))
      (node (ref "D5") (pin "A") (pinfunction "A_A") (pintype "passive"))
      (node (ref "D53") (pin "A") (pinfunction "A_A") (pintype "passive"))
      (node (ref "D61") (pin "A") (pinfunction "A_A") (pintype "passive"))
      (node (ref "U1") (pin "21") (pinfunction "SEG_E_21") (pintype "passive"))
    )
    (net (code "18") (name "/ROW5") (class "Default")
      (node (ref "D14") (pin "A") (pinfunction "A_A") (pintype "passive"))
      (node (ref "D22") (pin "A") (pinfunction "A_A") (pintype "passive"))
      (node (ref "D30") (pin "A") (pinfunction "A_A") (pintype "passive"))
      (node (ref "D38") (pin "A") (pinfunction "A_A") (pintype "passive"))
      (node (ref "D46") (pin "A") (pinfunction "A_A") (pintype "passive"))
      (node (ref "D54") (pin "A") (pinfunction "A_A") (pintype "passive"))
      (node (ref "D6") (pin "A") (pinfunction "A_A") (pintype "passive"))
      (node (ref "D62") (pin "A") (pinfunction "A_A") (pintype "passive"))
      (node (ref "U1") (pin "15") (pinfunction "SEG_F_15") (pintype "passive"))
    )
    (net (code "19") (name "/ROW6") (class "Default")
      (node (ref "D15") (pin "A") (pinfunction "A_A") (pintype "passive"))
      (node (ref "D23") (pin "A") (pinfunction "A_A") (pintype "passive"))
      (node (ref "D31") (pin "A") (pinfunction "A_A") (pintype "passive"))
      (node (ref "D39") (pin "A") (pinfunction "A_A") (pintype "passive"))
      (node (ref "D47") (pin "A") (pinfunction "A_A") (pintype "passive"))
      (node (ref "D55") (pin "A") (pinfunction "A_A") (pintype "passive"))
      (node (ref "D63") (pin "A") (pinfunction "A_A") (pintype "passive"))
      (node (ref "D7") (pin "A") (pinfunction "A_A") (pintype "passive"))
      (node (ref "U1") (pin "17") (pinfunction "SEG_G_17") (pintype "passive"))
    )
    (net (code "20") (name "/ROW7") (class "Default")
      (node (ref "D16") (pin "A") (pinfunction "A_A") (pintype "passive"))
      (node (ref "D24") (pin "A") (pinfunction "A_A") (pintype "passive"))
      (node (ref "D32") (pin "A") (pinfunction "A_A") (pintype "passive"))
      (node (ref "D40") (pin "A") (pinfunction "A_A") (pintype "passive"))
      (node (ref "D48") (pin "A") (pinfunction "A_A") (pintype "passive"))
      (node (ref "D56") (pin "A") (pinfunction "A_A") (pintype "passive"))
      (node (ref "D64") (pin "A") (pinfunction "A_A") (pintype "passive"))
      (node (ref "D8") (pin "A") (pinfunction "A_A") (pintype "passive"))
      (node (ref "U1") (pin "22") (pinfunction "SEG_DP_22") (pintype "passive"))
    )
    (net (code "21") (name "/SCK1") (class "Default")
      (node (ref "U1") (pin "13") (pinfunction "CLK_13") (pintype "input"))
      (node (ref "X2") (pin "6") (pinfunction "6_6") (pintype "passive"))
      (node (ref "X3") (pin "6") (pinfunction "6_6") (pintype "passive"))
    )
    (net (code "22") (name "/{slash}SS1") (class "Default")
      (node (ref "U1") (pin "12") (pinfunction "~{CS}_12") (pintype "input"))
      (node (ref "X2") (pin "5") (pinfunction "5_5") (pintype "passive"))
      (node (ref "X3") (pin "5") (pinfunction "5_5") (pintype "passive"))
    )
    (net (code "23") (name "GND") (class "Default")
      (node (ref "C1") (pin "1") (pinfunction "1_1") (pintype "passive"))
      (node (ref "R1") (pin "1") (pinfunction "1_1") (pintype "passive"))
      (node (ref "U1") (pin "4") (pinfunction "GND_4") (pintype "power_in"))
      (node (ref "U1") (pin "9") (pinfunction "GND_9") (pintype "power_in"))
      (node (ref "X2") (pin "4") (pinfunction "4_4") (pintype "passive"))
      (node (ref "X2") (pin "8") (pinfunction "8_8") (pintype "passive"))
      (node (ref "X3") (pin "4") (pinfunction "4_4") (pintype "passive"))
      (node (ref "X3") (pin "8") (pinfunction "8_8") (pintype "passive"))
    )
    (net (code "24") (name "Net-(U1-ISET)") (class "Default")
      (node (ref "R1") (pin "2") (pinfunction "2_2") (pintype "passive"))
      (node (ref "U1") (pin "18") (pinfunction "ISET_18") (pintype "passive"))
    )
    (net (code "25") (name "unconnected-(X1-Pad1)") (class "Default")
      (node (ref "X1") (pin "1") (pinfunction "1_1") (pintype "passive+no_connect"))
    )
    (net (code "26") (name "unconnected-(X1-Pad2)") (class "Default")
      (node (ref "X1") (pin "2") (pinfunction "2_2") (pintype "passive+no_connect"))
    )
    (net (code "27") (name "unconnected-(X1-Pad3)") (class "Default")
      (node (ref "X1") (pin "3") (pinfunction "3_3") (pintype "passive+no_connect"))
    )
    (net (code "28") (name "unconnected-(X1-Pad4)") (class "Default")
      (node (ref "X1") (pin "4") (pinfunction "4_4") (pintype "passive+no_connect"))
    )
    (net (code "29") (name "unconnected-(X1-Pad5)") (class "Default")
      (node (ref "X1") (pin "5") (pinfunction "5_5") (pintype "passive+no_connect"))
    )
    (net (code "30") (name "unconnected-(X1-Pad6)") (class "Default")
      (node (ref "X1") (pin "6") (pinfunction "6_6") (pintype "passive+no_connect"))
    )
    (net (code "31") (name "unconnected-(X1-Pad7)") (class "Default")
      (node (ref "X1") (pin "7") (pinfunction "7_7") (pintype "passive+no_connect"))
    )
    (net (code "32") (name "unconnected-(X1-Pad8)") (class "Default")
      (node (ref "X1") (pin "8") (pinfunction "8_8") (pintype "passive+no_connect"))
    )
    (net (code "33") (name "unconnected-(X4-Pad1)") (class "Default")
      (node (ref "X4") (pin "1") (pinfunction "1_1") (pintype "passive+no_connect"))
    )
    (net (code "34") (name "unconnected-(X4-Pad2)") (class "Default")
      (node (ref "X4") (pin "2") (pinfunction "2_2") (pintype "passive+no_connect"))
    )
    (net (code "35") (name "unconnected-(X4-Pad3)") (class "Default")
      (node (ref "X4") (pin "3") (pinfunction "3_3") (pintype "passive+no_connect"))
    )
    (net (code "36") (name "unconnected-(X4-Pad4)") (class "Default")
      (node (ref "X4") (pin "4") (pinfunction "4_4") (pintype "passive+no_connect"))
    )
    (net (code "37") (name "unconnected-(X4-Pad5)") (class "Default")
      (node (ref "X4") (pin "5") (pinfunction "5_5") (pintype "passive+no_connect"))
    )
    (net (code "38") (name "unconnected-(X4-Pad6)") (class "Default")
      (node (ref "X4") (pin "6") (pinfunction "6_6") (pintype "passive+no_connect"))
    )
    (net (code "39") (name "unconnected-(X4-Pad7)") (class "Default")
      (node (ref "X4") (pin "7") (pinfunction "7_7") (pintype "passive+no_connect"))
    )
    (net (code "40") (name "unconnected-(X4-Pad8)") (class "Default")
      (node (ref "X4") (pin "8") (pinfunction "8_8") (pintype "passive+no_connect"))
    )
  )
)
